# Bluetooth.net
KiCad netlist of a schematic drawn in Altium Designer
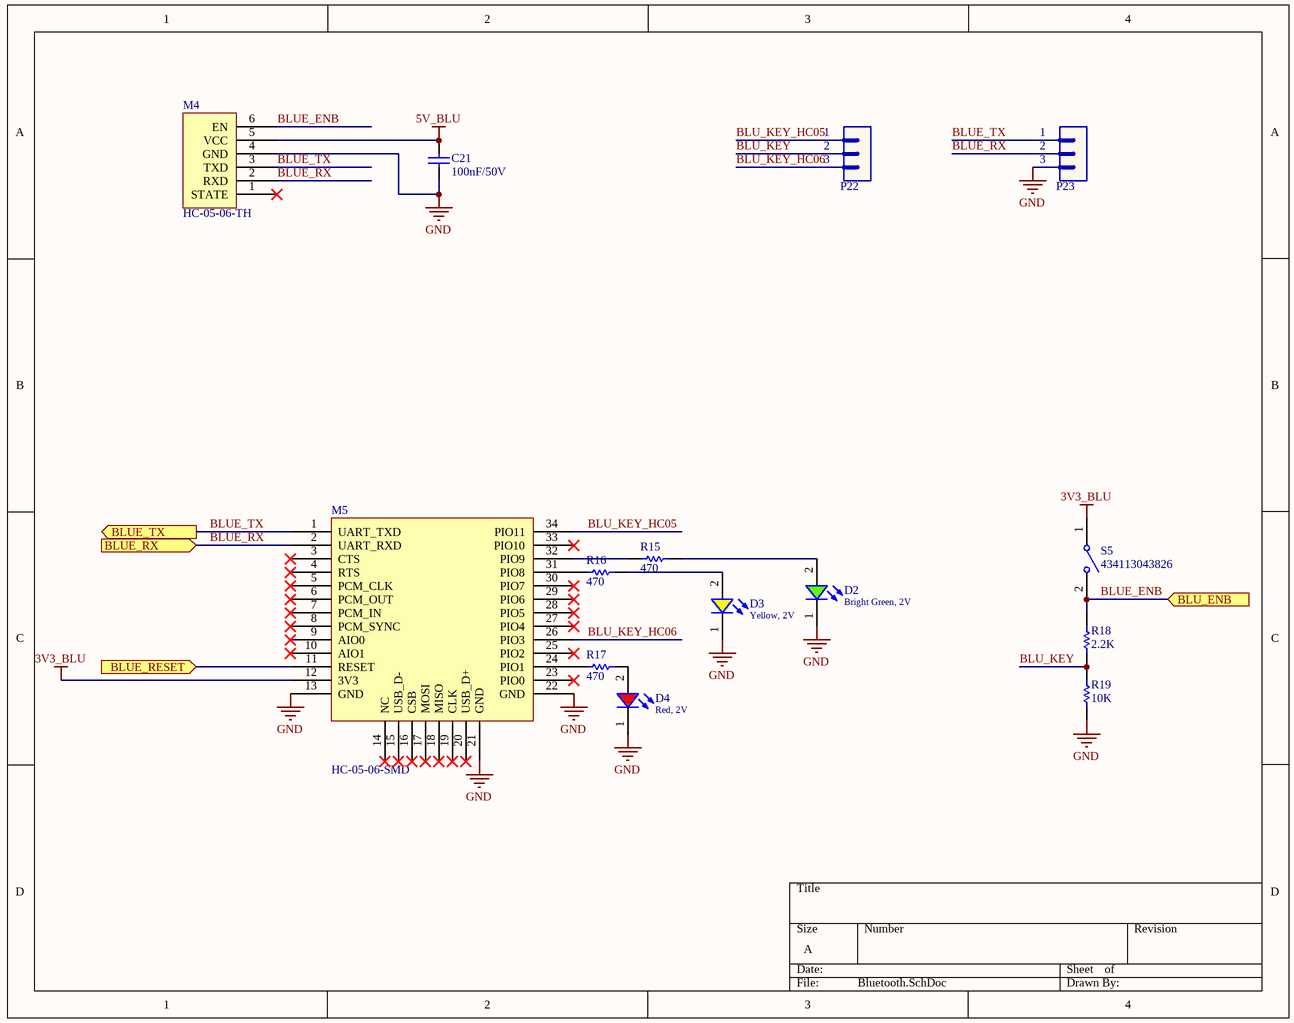
[diagram p0: Bluetooth.SchDoc]

(export (version "E")
  (design (tool "Eeschema 10.0.6"))
  (components
    (comp (ref "C21")
      (value "100nF/50V")
      (footprint "CAP-SM-0805")
      (description "CAP CER 0.1UF 50V Y5V 0805")
      (fields
        (field (name "MANUFACTURER") "Samsung Electro-Mechanics")
        (field (name "MANUFACTURER PART NUMBER") "CL21F104ZBCNNNC")
      )
      (libsource (lib "Capacitor") (part "Cap-100nF-50V-0805"))
    )
    (comp (ref "D2")
      (value "Bright Green, 2V")
      (footprint "WL-SMCW_0805")
      (description "WL-SMCW SMT Mono-color Chip LED Waterclear, size 0805, Bright Green, 2V, 140deg")
      (fields (field (name "PART NUMBER") "150080VS75000") (field (name "PUBLISHER") "Wurth Elektronik"))
      (libsource (lib "LED_150060BS75000_Altium_WL-SMCW_rev20a") (part "150080VS75000"))
    )
    (comp (ref "D3")
      (value "Yellow, 2V")
      (footprint "WL-SMCW_0805")
      (description "WL-SMCW SMT Mono-color Chip LED Waterclear, size 0805, Yellow, 2V, 140deg")
      (fields (field (name "PART NUMBER") "150080YS75000") (field (name "PUBLISHER") "Wurth Elektronik"))
      (libsource (lib "LED_150060BS75000_Altium_WL-SMCW_rev20a") (part "150080YS75000"))
    )
    (comp (ref "D4")
      (value "Red, 2V")
      (footprint "WL-SMCW_0805")
      (description "WL-SMCW SMT Mono-color Chip LED Waterclear, size 0805, Red, 2V, 140deg")
      (fields (field (name "PART NUMBER") "150080RS75000") (field (name "PUBLISHER") "Wurth Elektronik"))
      (libsource (lib "LED_150060BS75000_Altium_WL-SMCW_rev20a") (part "150080RS75000"))
    )
    (comp (ref "M4")
      (value "HC-05-06-TH")
      (footprint "HC-05-06-TH")
      (fields (field (name "LOCAL SUPPLIER PART NUMBER") "HS000882"))
      (libsource (lib "PIFWRoBot") (part "HC-05-06-TH"))
    )
    (comp (ref "M5")
      (value "HC-05-06-SMD")
      (footprint "HC-05-06-SMD")
      (fields (field (name "LOCAL SUPPLIER PART NUMBER") "HS000881"))
      (libsource (lib "PIFWRoBot") (part "HC-05-06-SMD"))
    )
    (comp (ref "P22")
      (value "Header 3")
      (footprint "JP3")
      (description "Header, 3-Pin")
      (fields (field (name "PUBLISHER") "Altium Limited"))
      (libsource (lib "Header-connector") (part "Header 3"))
    )
    (comp (ref "P23")
      (value "Header 3")
      (footprint "JP3")
      (description "Header, 3-Pin")
      (fields (field (name "PUBLISHER") "Altium Limited"))
      (libsource (lib "Header-connector") (part "Header 3"))
    )
    (comp (ref "R15")
      (value "470")
      (footprint "Resistor:RES-SM-0805")
      (description "RES 470 OHM JUMPER 0805")
      (fields
        (field (name "MANUFACTURER") "YAG6006CT-ND")
        (field (name "MANUFACTURER PART NUMBER") "PE0805FRF7W0R047L")
      )
      (libsource (lib "Resistor") (part "Res-470-0805"))
    )
    (comp (ref "R16")
      (value "470")
      (footprint "Resistor:RES-SM-0805")
      (description "RES 470 OHM JUMPER 0805")
      (fields
        (field (name "MANUFACTURER") "YAG6006CT-ND")
        (field (name "MANUFACTURER PART NUMBER") "PE0805FRF7W0R047L")
      )
      (libsource (lib "Resistor") (part "Res-470-0805"))
    )
    (comp (ref "R17")
      (value "470")
      (footprint "Resistor:RES-SM-0805")
      (description "RES 470 OHM JUMPER 0805")
      (fields
        (field (name "MANUFACTURER") "YAG6006CT-ND")
        (field (name "MANUFACTURER PART NUMBER") "PE0805FRF7W0R047L")
      )
      (libsource (lib "Resistor") (part "Res-470-0805"))
    )
    (comp (ref "R18")
      (value "2.2K")
      (footprint "Resistor:RES-SM-0805")
      (description "RES SMD 2.2K OHM 1% 1/8W 0805")
      (fields
        (field (name "MANUFACTURER") "TE Connectivity Passive Product")
        (field (name "MANUFACTURER PART NUMBER") "CRG0805F2K2")
      )
      (libsource (lib "Resistor") (part "Res-2.2K-0805"))
    )
    (comp (ref "R19")
      (value "10K")
      (footprint "Resistor:RES-SM-0805")
      (description "RES 10K OHM 1% 1/4W 0805")
      (fields
        (field (name "MANUFACTURER") "Stackpole Electronics Inc")
        (field (name "MANUFACTURER PART NUMBER") "RNCP0805FTD10K0")
      )
      (libsource (lib "Resistor") (part "Res-10k-0805"))
    )
    (comp (ref "S5")
      (value "434113043826")
      (footprint "434113043826")
      (description "WS-TASV J-Bend SMT Tact Switch 6x3.5mm, height 4.3mm, 260gf")
      (fields (field (name "PUBLISHER") "Wurth Elektronik"))
      (libsource (lib "434113043826_Altium_WS-TASV_rev20a") (part "434113043826"))
    )
  )
  (nets
    (net (code "1") (name "/BLUE_ENB") (class "Default")
      (node (ref "M4") (pin "6") (pinfunction "EN_6") (pintype "passive"))
      (node (ref "R18") (pin "2") (pinfunction "2_2") (pintype "passive"))
      (node (ref "S5") (pin "2") (pinfunction "2_2") (pintype "passive"))
    )
    (net (code "2") (name "/BLUE_RESET") (class "Default")
      (node (ref "M5") (pin "11") (pinfunction "RESET_11") (pintype "passive"))
    )
    (net (code "3") (name "/BLUE_RX") (class "Default")
      (node (ref "M4") (pin "2") (pinfunction "RXD_2") (pintype "passive"))
      (node (ref "M5") (pin "2") (pinfunction "UART_RXD_2") (pintype "passive"))
      (node (ref "P23") (pin "2") (pinfunction "2_2") (pintype "passive"))
    )
    (net (code "4") (name "/BLUE_TX") (class "Default")
      (node (ref "M4") (pin "3") (pinfunction "TXD_3") (pintype "passive"))
      (node (ref "M5") (pin "1") (pinfunction "UART_TXD_1") (pintype "passive"))
      (node (ref "P23") (pin "1") (pinfunction "1_1") (pintype "passive"))
    )
    (net (code "5") (name "/BLU_KEY") (class "Default")
      (node (ref "P22") (pin "2") (pinfunction "2_2") (pintype "passive"))
      (node (ref "R18") (pin "1") (pinfunction "1_1") (pintype "passive"))
      (node (ref "R19") (pin "2") (pinfunction "2_2") (pintype "passive"))
    )
    (net (code "6") (name "/BLU_KEY_HC05") (class "Default")
      (node (ref "M5") (pin "34") (pinfunction "PIO11_34") (pintype "passive"))
      (node (ref "P22") (pin "1") (pinfunction "1_1") (pintype "passive"))
    )
    (net (code "7") (name "/BLU_KEY_HC06") (class "Default")
      (node (ref "M5") (pin "26") (pinfunction "PIO3_26") (pintype "passive"))
      (node (ref "P22") (pin "3") (pinfunction "3_3") (pintype "passive"))
    )
    (net (code "8") (name "3V3_BLU") (class "Default")
      (node (ref "M5") (pin "12") (pinfunction "3V3_12") (pintype "passive"))
      (node (ref "S5") (pin "1") (pinfunction "1_1") (pintype "passive"))
    )
    (net (code "9") (name "5V_BLU") (class "Default")
      (node (ref "C21") (pin "2") (pinfunction "2_2") (pintype "passive"))
      (node (ref "M4") (pin "5") (pinfunction "VCC_5") (pintype "passive"))
    )
    (net (code "10") (name "GND") (class "Default")
      (node (ref "C21") (pin "1") (pinfunction "1_1") (pintype "passive"))
      (node (ref "D2") (pin "1") (pinfunction "K_1") (pintype "passive"))
      (node (ref "D3") (pin "1") (pinfunction "K_1") (pintype "passive"))
      (node (ref "D4") (pin "1") (pinfunction "K_1") (pintype "passive"))
      (node (ref "M4") (pin "4") (pinfunction "GND_4") (pintype "passive"))
      (node (ref "M5") (pin "13") (pinfunction "GND_13") (pintype "passive"))
      (node (ref "M5") (pin "21") (pinfunction "GND_21") (pintype "passive"))
      (node (ref "M5") (pin "22") (pinfunction "GND_22") (pintype "passive"))
      (node (ref "P23") (pin "3") (pinfunction "3_3") (pintype "passive"))
      (node (ref "R19") (pin "1") (pinfunction "1_1") (pintype "passive"))
    )
    (net (code "11") (name "Net-(D2-A)") (class "Default")
      (node (ref "D2") (pin "2") (pinfunction "A_2") (pintype "passive"))
      (node (ref "R15") (pin "2") (pinfunction "2_2") (pintype "passive"))
    )
    (net (code "12") (name "Net-(D3-A)") (class "Default")
      (node (ref "D3") (pin "2") (pinfunction "A_2") (pintype "passive"))
      (node (ref "R16") (pin "2") (pinfunction "2_2") (pintype "passive"))
    )
    (net (code "13") (name "Net-(D4-A)") (class "Default")
      (node (ref "D4") (pin "2") (pinfunction "A_2") (pintype "passive"))
      (node (ref "R17") (pin "2") (pinfunction "2_2") (pintype "passive"))
    )
    (net (code "14") (name "Net-(M5-PIO1)") (class "Default")
      (node (ref "M5") (pin "24") (pinfunction "PIO1_24") (pintype "passive"))
      (node (ref "R17") (pin "1") (pinfunction "1_1") (pintype "passive"))
    )
    (net (code "15") (name "Net-(M5-PIO8)") (class "Default")
      (node (ref "M5") (pin "31") (pinfunction "PIO8_31") (pintype "passive"))
      (node (ref "R16") (pin "1") (pinfunction "1_1") (pintype "passive"))
    )
    (net (code "16") (name "Net-(M5-PIO9)") (class "Default")
      (node (ref "M5") (pin "32") (pinfunction "PIO9_32") (pintype "passive"))
      (node (ref "R15") (pin "1") (pinfunction "1_1") (pintype "passive"))
    )
    (net (code "17") (name "unconnected-(M4-STATE-Pad1)") (class "Default")
      (node (ref "M4") (pin "1") (pinfunction "STATE_1") (pintype "passive+no_connect"))
    )
    (net (code "18") (name "unconnected-(M5-AIO0-Pad9)") (class "Default")
      (node (ref "M5") (pin "9") (pinfunction "AIO0_9") (pintype "passive+no_connect"))
    )
    (net (code "19") (name "unconnected-(M5-AIO1-Pad10)") (class "Default")
      (node (ref "M5") (pin "10") (pinfunction "AIO1_10") (pintype "passive+no_connect"))
    )
    (net (code "20") (name "unconnected-(M5-CLK-Pad19)") (class "Default")
      (node (ref "M5") (pin "19") (pinfunction "CLK_19") (pintype "passive+no_connect"))
    )
    (net (code "21") (name "unconnected-(M5-CSB-Pad16)") (class "Default")
      (node (ref "M5") (pin "16") (pinfunction "CSB_16") (pintype "passive+no_connect"))
    )
    (net (code "22") (name "unconnected-(M5-CTS-Pad3)") (class "Default")
      (node (ref "M5") (pin "3") (pinfunction "CTS_3") (pintype "passive+no_connect"))
    )
    (net (code "23") (name "unconnected-(M5-MISO-Pad18)") (class "Default")
      (node (ref "M5") (pin "18") (pinfunction "MISO_18") (pintype "passive+no_connect"))
    )
    (net (code "24") (name "unconnected-(M5-MOSI-Pad17)") (class "Default")
      (node (ref "M5") (pin "17") (pinfunction "MOSI_17") (pintype "passive+no_connect"))
    )
    (net (code "25") (name "unconnected-(M5-NC-Pad14)") (class "Default")
      (node (ref "M5") (pin "14") (pinfunction "NC_14") (pintype "passive+no_connect"))
    )
    (net (code "26") (name "unconnected-(M5-PCM_CLK-Pad5)") (class "Default")
      (node (ref "M5") (pin "5") (pinfunction "PCM_CLK_5") (pintype "passive+no_connect"))
    )
    (net (code "27") (name "unconnected-(M5-PCM_IN-Pad7)") (class "Default")
      (node (ref "M5") (pin "7") (pinfunction "PCM_IN_7") (pintype "passive+no_connect"))
    )
    (net (code "28") (name "unconnected-(M5-PCM_OUT-Pad6)") (class "Default")
      (node (ref "M5") (pin "6") (pinfunction "PCM_OUT_6") (pintype "passive+no_connect"))
    )
    (net (code "29") (name "unconnected-(M5-PCM_SYNC-Pad8)") (class "Default")
      (node (ref "M5") (pin "8") (pinfunction "PCM_SYNC_8") (pintype "passive+no_connect"))
    )
    (net (code "30") (name "unconnected-(M5-PIO0-Pad23)") (class "Default")
      (node (ref "M5") (pin "23") (pinfunction "PIO0_23") (pintype "passive+no_connect"))
    )
    (net (code "31") (name "unconnected-(M5-PIO2-Pad25)") (class "Default")
      (node (ref "M5") (pin "25") (pinfunction "PIO2_25") (pintype "passive+no_connect"))
    )
    (net (code "32") (name "unconnected-(M5-PIO4-Pad27)") (class "Default")
      (node (ref "M5") (pin "27") (pinfunction "PIO4_27") (pintype "passive+no_connect"))
    )
    (net (code "33") (name "unconnected-(M5-PIO5-Pad28)") (class "Default")
      (node (ref "M5") (pin "28") (pinfunction "PIO5_28") (pintype "passive+no_connect"))
    )
    (net (code "34") (name "unconnected-(M5-PIO6-Pad29)") (class "Default")
      (node (ref "M5") (pin "29") (pinfunction "PIO6_29") (pintype "passive+no_connect"))
    )
    (net (code "35") (name "unconnected-(M5-PIO7-Pad30)") (class "Default")
      (node (ref "M5") (pin "30") (pinfunction "PIO7_30") (pintype "passive+no_connect"))
    )
    (net (code "36") (name "unconnected-(M5-PIO10-Pad33)") (class "Default")
      (node (ref "M5") (pin "33") (pinfunction "PIO10_33") (pintype "passive+no_connect"))
    )
    (net (code "37") (name "unconnected-(M5-RTS-Pad4)") (class "Default")
      (node (ref "M5") (pin "4") (pinfunction "RTS_4") (pintype "passive+no_connect"))
    )
    (net (code "38") (name "unconnected-(M5-USB_D+-Pad20)") (class "Default")
      (node (ref "M5") (pin "20") (pinfunction "USB_D+_20") (pintype "passive+no_connect"))
    )
    (net (code "39") (name "unconnected-(M5-USB_D--Pad15)") (class "Default")
      (node (ref "M5") (pin "15") (pinfunction "USB_D-_15") (pintype "passive+no_connect"))
    )
  )
)
